# phasor.net
KiCad netlist of a schematic drawn in EAGLE
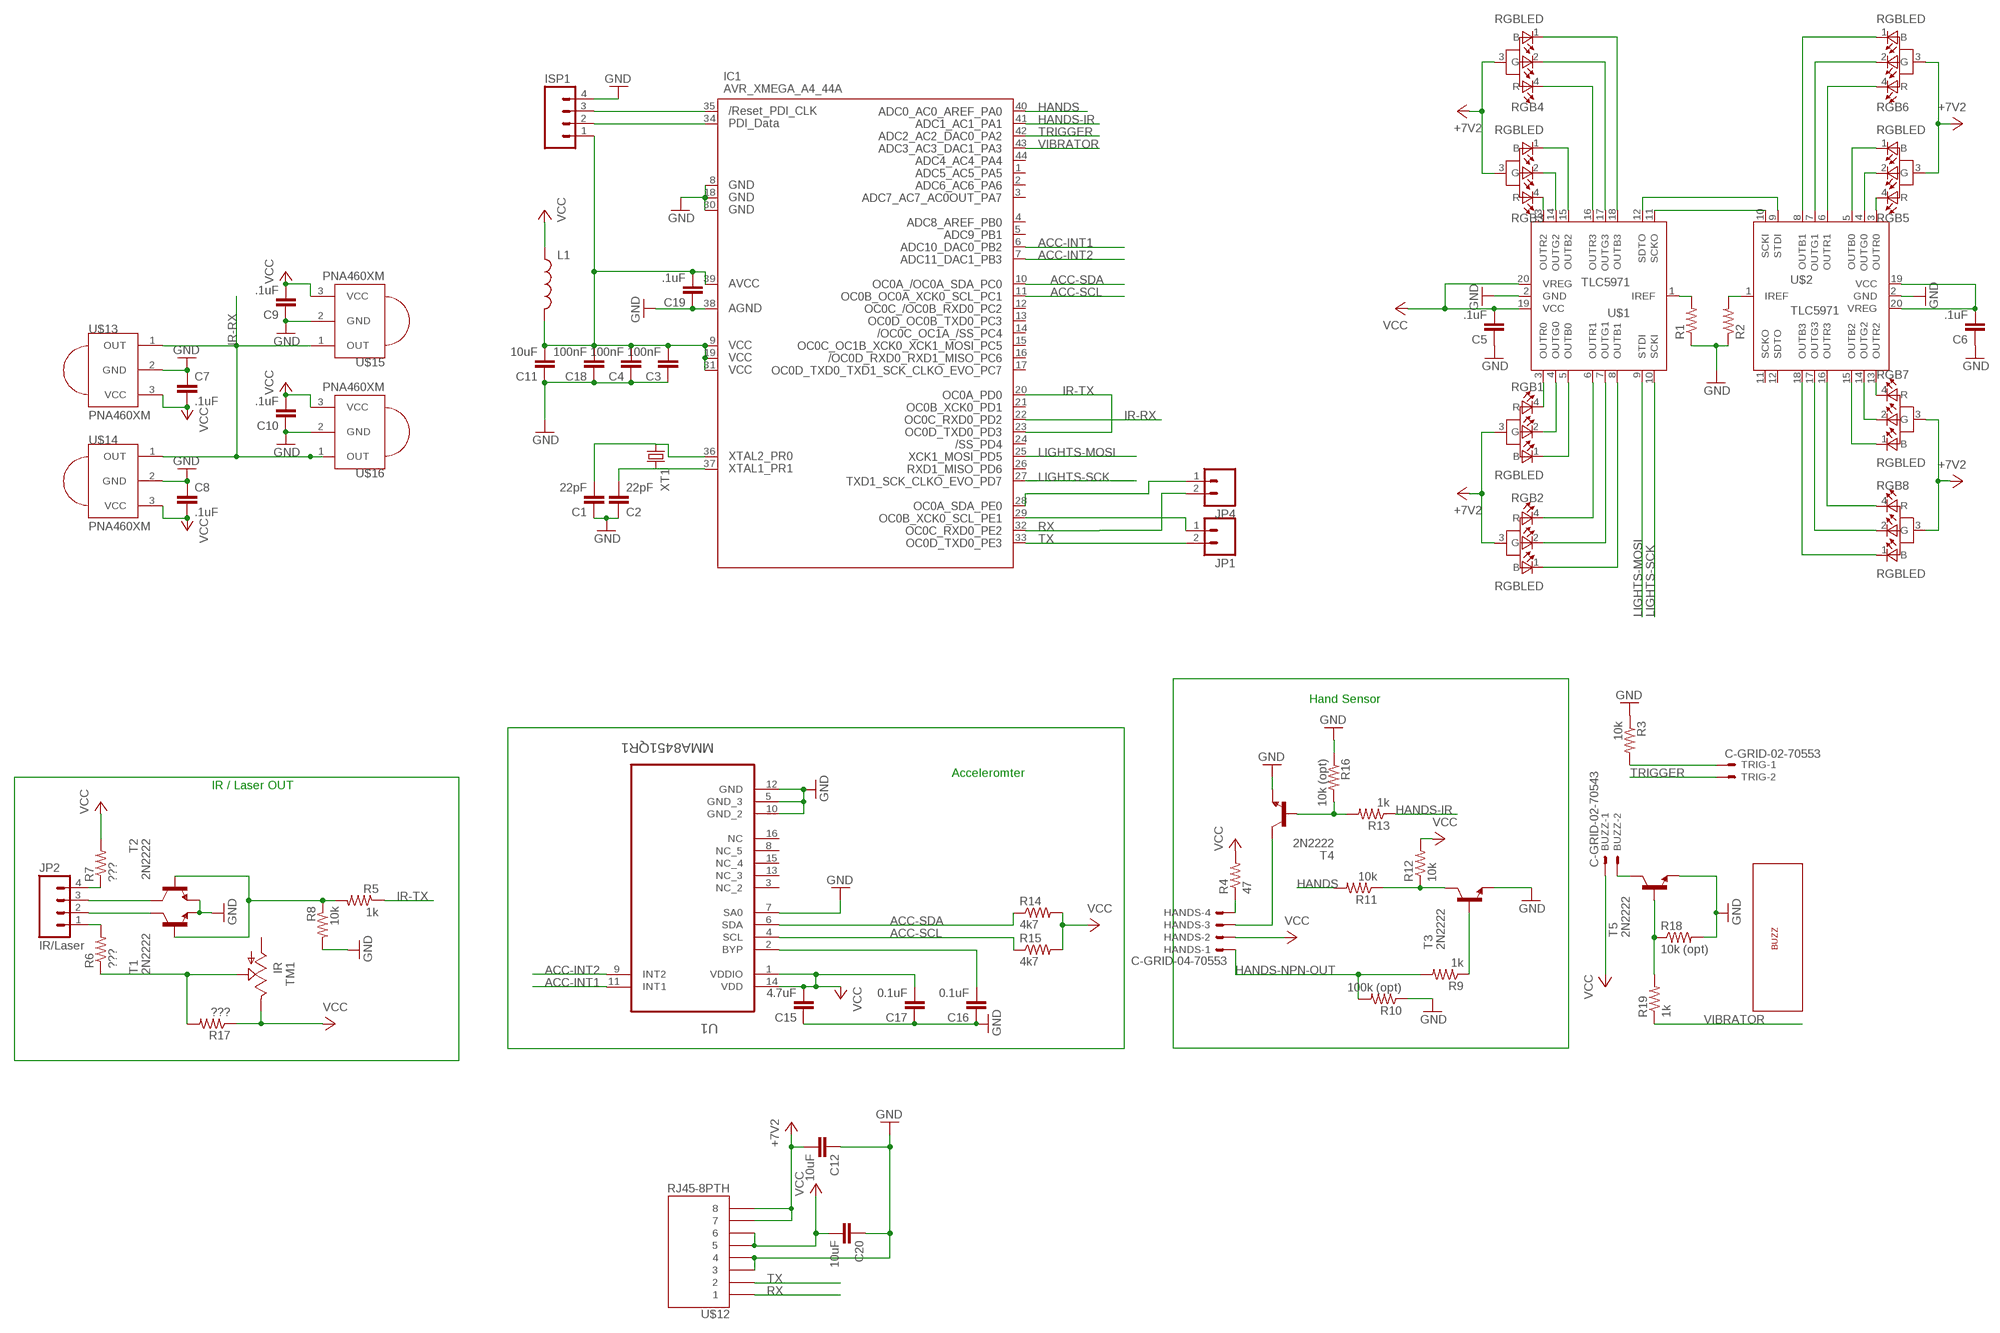
[diagram p0: schematic, sheet 1]

(export (version "E")
  (design (tool "Eeschema 10.0.6"))
  (components
    (comp (ref "BUZZ")
      (value "C-GRID-02-70543")
      (footprint "eagle-import:70543-02")
      (libsource (lib "eagle-import") (part "C-GRID-02-70543"))
    )
    (comp (ref "C1")
      (value "22pF")
      (footprint "eagle-import:CAP-PTH-SMALL")
      (libsource (lib "eagle-import") (part "CAPPTH"))
    )
    (comp (ref "C2")
      (value "22pF")
      (footprint "eagle-import:CAP-PTH-SMALL")
      (libsource (lib "eagle-import") (part "CAPPTH"))
    )
    (comp (ref "C3")
      (value "100nF")
      (footprint "eagle-import:0603-CAP")
      (libsource (lib "eagle-import") (part "CAP0603-CAP"))
    )
    (comp (ref "C4")
      (value "100nF")
      (footprint "eagle-import:0603-CAP")
      (libsource (lib "eagle-import") (part "CAP0603-CAP"))
    )
    (comp (ref "C5")
      (value ".1uF")
      (footprint "eagle-import:CAP-PTH-SMALL")
      (libsource (lib "eagle-import") (part "CAPPTH"))
    )
    (comp (ref "C6")
      (value ".1uF")
      (footprint "eagle-import:CAP-PTH-SMALL")
      (libsource (lib "eagle-import") (part "CAPPTH"))
    )
    (comp (ref "C7")
      (value ".1uF")
      (footprint "eagle-import:CAP-PTH-SMALL")
      (libsource (lib "eagle-import") (part "CAPPTH"))
    )
    (comp (ref "C8")
      (value ".1uF")
      (footprint "eagle-import:CAP-PTH-SMALL")
      (libsource (lib "eagle-import") (part "CAPPTH"))
    )
    (comp (ref "C9")
      (value ".1uF")
      (footprint "eagle-import:CAP-PTH-SMALL")
      (libsource (lib "eagle-import") (part "CAPPTH"))
    )
    (comp (ref "C10")
      (value ".1uF")
      (footprint "eagle-import:CAP-PTH-SMALL")
      (libsource (lib "eagle-import") (part "CAPPTH"))
    )
    (comp (ref "C11")
      (value "10uF")
      (footprint "eagle-import:1206")
      (libsource (lib "eagle-import") (part "CAP1206"))
    )
    (comp (ref "C12")
      (value "10uF")
      (footprint "eagle-import:1206")
      (libsource (lib "eagle-import") (part "CAP1206"))
    )
    (comp (ref "C15")
      (value "4.7uF")
      (footprint "eagle-import:0805")
      (libsource (lib "eagle-import") (part "CAP0805"))
    )
    (comp (ref "C16")
      (value "0.1uF")
      (footprint "eagle-import:0603-CAP")
      (libsource (lib "eagle-import") (part "CAP0603-CAP"))
    )
    (comp (ref "C17")
      (value "0.1uF")
      (footprint "eagle-import:0603-CAP")
      (libsource (lib "eagle-import") (part "CAP0603-CAP"))
    )
    (comp (ref "C18")
      (value "100nF")
      (footprint "eagle-import:0603-CAP")
      (libsource (lib "eagle-import") (part "CAP0603-CAP"))
    )
    (comp (ref "C19")
      (value ".1uF")
      (footprint "eagle-import:0603-CAP")
      (libsource (lib "eagle-import") (part "CAP0603-CAP"))
    )
    (comp (ref "C20")
      (value "10uF")
      (footprint "eagle-import:1206")
      (libsource (lib "eagle-import") (part "CAP1206"))
    )
    (comp (ref "HANDS")
      (value "C-GRID-04-70553")
      (footprint "eagle-import:70553-04")
      (libsource (lib "eagle-import") (part "C-GRID-04-70553"))
    )
    (comp (ref "IC1")
      (value "AVR_XMEGA_A4_44A")
      (footprint "eagle-import:TQFP44")
      (libsource (lib "eagle-import") (part "AVR_XMEGA_A4_44A"))
    )
    (comp (ref "ISP1")
      (value "M04LOCK")
      (footprint "eagle-import:1X04_LOCK")
      (libsource (lib "eagle-import") (part "M04LOCK"))
    )
    (comp (ref "JP1")
      (value "M02PTH")
      (footprint "eagle-import:1X02")
      (libsource (lib "eagle-import") (part "M02PTH"))
    )
    (comp (ref "JP2")
      (value "IR/Laser")
      (footprint "eagle-import:1X04_LOCK")
      (libsource (lib "eagle-import") (part "M04LOCK"))
    )
    (comp (ref "JP4")
      (value "M02PTH")
      (footprint "eagle-import:1X02")
      (libsource (lib "eagle-import") (part "M02PTH"))
    )
    (comp (ref "L1")
      (value "INDUCTOR1206H*")
      (footprint "eagle-import:1206")
      (libsource (lib "eagle-import") (part "INDUCTORH1206"))
    )
    (comp (ref "R1")
      (value "R-US_0204/7")
      (footprint "eagle-import:0204_7")
      (libsource (lib "eagle-import") (part "R-US_0204/7"))
    )
    (comp (ref "R2")
      (value "R-US_0204/7")
      (footprint "eagle-import:0204_7")
      (libsource (lib "eagle-import") (part "R-US_0204/7"))
    )
    (comp (ref "R3")
      (value "10k")
      (footprint "eagle-import:0204_7")
      (libsource (lib "eagle-import") (part "R-US_0204/7"))
    )
    (comp (ref "R4")
      (value "47")
      (footprint "eagle-import:0204_7")
      (libsource (lib "eagle-import") (part "R-US_0204/7"))
    )
    (comp (ref "R5")
      (value "1k")
      (footprint "eagle-import:0204_7")
      (libsource (lib "eagle-import") (part "R-US_0204/7"))
    )
    (comp (ref "R6")
      (value "???")
      (footprint "eagle-import:0204_7")
      (libsource (lib "eagle-import") (part "R-US_0204/7"))
    )
    (comp (ref "R7")
      (value "???")
      (footprint "eagle-import:0204_7")
      (libsource (lib "eagle-import") (part "R-US_0204/7"))
    )
    (comp (ref "R8")
      (value "10k")
      (footprint "eagle-import:0204_7")
      (libsource (lib "eagle-import") (part "R-US_0204/7"))
    )
    (comp (ref "R9")
      (value "1k")
      (footprint "eagle-import:0204_7")
      (libsource (lib "eagle-import") (part "R-US_0204/7"))
    )
    (comp (ref "R10")
      (value "100k (opt)")
      (footprint "eagle-import:0204_7")
      (libsource (lib "eagle-import") (part "R-US_0204/7"))
    )
    (comp (ref "R11")
      (value "10k")
      (footprint "eagle-import:0204_7")
      (libsource (lib "eagle-import") (part "R-US_0204/7"))
    )
    (comp (ref "R12")
      (value "10k")
      (footprint "eagle-import:0204_7")
      (libsource (lib "eagle-import") (part "R-US_0204/7"))
    )
    (comp (ref "R13")
      (value "1k")
      (footprint "eagle-import:0204_7")
      (libsource (lib "eagle-import") (part "R-US_0204/7"))
    )
    (comp (ref "R14")
      (value "4k7")
      (footprint "eagle-import:0204_7")
      (libsource (lib "eagle-import") (part "R-US_0204/7"))
    )
    (comp (ref "R15")
      (value "4k7")
      (footprint "eagle-import:0204_7")
      (libsource (lib "eagle-import") (part "R-US_0204/7"))
    )
    (comp (ref "R16")
      (value "10k (opt)")
      (footprint "eagle-import:0204_7")
      (libsource (lib "eagle-import") (part "R-US_0204/7"))
    )
    (comp (ref "R17")
      (value "???")
      (footprint "eagle-import:0204_7")
      (libsource (lib "eagle-import") (part "R-US_0204/7"))
    )
    (comp (ref "R18")
      (value "10k (opt)")
      (footprint "eagle-import:0204_7")
      (libsource (lib "eagle-import") (part "R-US_0204/7"))
    )
    (comp (ref "R19")
      (value "1k")
      (footprint "eagle-import:0204_7")
      (libsource (lib "eagle-import") (part "R-US_0204/7"))
    )
    (comp (ref "RGB1")
      (value "RGBLED")
      (footprint "eagle-import:RGB-LED-10MM-COMMON-ANODE")
      (libsource (lib "eagle-import") (part "RGBLED"))
    )
    (comp (ref "RGB2")
      (value "RGBLED")
      (footprint "eagle-import:RGB-LED-10MM-COMMON-ANODE")
      (libsource (lib "eagle-import") (part "RGBLED"))
    )
    (comp (ref "RGB3")
      (value "RGBLED")
      (footprint "eagle-import:RGB-LED-10MM-COMMON-ANODE")
      (libsource (lib "eagle-import") (part "RGBLED"))
    )
    (comp (ref "RGB4")
      (value "RGBLED")
      (footprint "eagle-import:RGB-LED-10MM-COMMON-ANODE")
      (libsource (lib "eagle-import") (part "RGBLED"))
    )
    (comp (ref "RGB5")
      (value "RGBLED")
      (footprint "eagle-import:RGB-LED-10MM-COMMON-ANODE")
      (libsource (lib "eagle-import") (part "RGBLED"))
    )
    (comp (ref "RGB6")
      (value "RGBLED")
      (footprint "eagle-import:RGB-LED-10MM-COMMON-ANODE")
      (libsource (lib "eagle-import") (part "RGBLED"))
    )
    (comp (ref "RGB7")
      (value "RGBLED")
      (footprint "eagle-import:RGB-LED-10MM-COMMON-ANODE")
      (libsource (lib "eagle-import") (part "RGBLED"))
    )
    (comp (ref "RGB8")
      (value "RGBLED")
      (footprint "eagle-import:RGB-LED-10MM-COMMON-ANODE")
      (libsource (lib "eagle-import") (part "RGBLED"))
    )
    (comp (ref "T1")
      (value "2N2222")
      (footprint "eagle-import:TO92-EBC-OVAL")
      (libsource (lib "eagle-import") (part "2N2222"))
    )
    (comp (ref "T2")
      (value "2N2222")
      (footprint "eagle-import:TO92-EBC-OVAL")
      (libsource (lib "eagle-import") (part "2N2222"))
    )
    (comp (ref "T3")
      (value "2N2222")
      (footprint "eagle-import:TO92-EBC-OVAL")
      (libsource (lib "eagle-import") (part "2N2222"))
    )
    (comp (ref "T4")
      (value "2N2222")
      (footprint "eagle-import:TO92-EBC-OVAL")
      (libsource (lib "eagle-import") (part "2N2222"))
    )
    (comp (ref "T5")
      (value "2N2222")
      (footprint "eagle-import:TO92-EBC-OVAL")
      (libsource (lib "eagle-import") (part "2N2222"))
    )
    (comp (ref "TM1")
      (value "IR")
      (footprint "eagle-import:B25P")
      (libsource (lib "eagle-import") (part "TRIM_US-B25P"))
    )
    (comp (ref "TRIG")
      (value "C-GRID-02-70553")
      (footprint "eagle-import:70553-02")
      (libsource (lib "eagle-import") (part "C-GRID-02-70553"))
    )
    (comp (ref "U$1")
      (value "TLC5971")
      (footprint "eagle-import:SSOP20")
      (libsource (lib "eagle-import") (part "TLC5971"))
    )
    (comp (ref "U$2")
      (value "TLC5971")
      (footprint "eagle-import:SSOP20")
      (libsource (lib "eagle-import") (part "TLC5971"))
    )
    (comp (ref "U$3")
      (value "VIB-CAPSULE")
      (footprint "eagle-import:VIB-CAPSULE")
      (libsource (lib "eagle-import") (part "VIB-CAPSULE"))
    )
    (comp (ref "U$12")
      (value "RJ45-8PTH")
      (footprint "eagle-import:RJ45-8")
      (libsource (lib "eagle-import") (part "RJ45-8PTH"))
    )
    (comp (ref "U$13")
      (value "PNA460XM")
      (footprint "eagle-import:PNA460XM")
      (libsource (lib "eagle-import") (part "PNA460XM"))
    )
    (comp (ref "U$14")
      (value "PNA460XM")
      (footprint "eagle-import:PNA460XM")
      (libsource (lib "eagle-import") (part "PNA460XM"))
    )
    (comp (ref "U$15")
      (value "PNA460XM")
      (footprint "eagle-import:PNA460XM")
      (libsource (lib "eagle-import") (part "PNA460XM"))
    )
    (comp (ref "U$16")
      (value "PNA460XM")
      (footprint "eagle-import:PNA460XM")
      (libsource (lib "eagle-import") (part "PNA460XM"))
    )
    (comp (ref "U1")
      (value "MMA8451QR1")
      (footprint "eagle-import:QFN50P300X300X100-16N")
      (libsource (lib "eagle-import") (part "MMA8451QR1"))
    )
    (comp (ref "XT1")
      (value "CRYSTALHC49US")
      (footprint "eagle-import:HC49US")
      (libsource (lib "eagle-import") (part "CRYSTALHC49US"))
    )
  )
  (nets
    (net (code "1") (name "/+7V2") (class "Default")
      (node (ref "C12") (pin "2") (pinfunction "2_2") (pintype "passive"))
      (node (ref "RGB1") (pin "3") (pinfunction "VCC_3") (pintype "passive"))
      (node (ref "RGB2") (pin "3") (pinfunction "VCC_3") (pintype "passive"))
      (node (ref "RGB3") (pin "3") (pinfunction "VCC_3") (pintype "passive"))
      (node (ref "RGB4") (pin "3") (pinfunction "VCC_3") (pintype "passive"))
      (node (ref "RGB5") (pin "3") (pinfunction "VCC_3") (pintype "passive"))
      (node (ref "RGB6") (pin "3") (pinfunction "VCC_3") (pintype "passive"))
      (node (ref "RGB7") (pin "3") (pinfunction "VCC_3") (pintype "passive"))
      (node (ref "RGB8") (pin "3") (pinfunction "VCC_3") (pintype "passive"))
      (node (ref "U$12") (pin "7") (pinfunction "7_7") (pintype "bidirectional"))
      (node (ref "U$12") (pin "8") (pinfunction "8_8") (pintype "bidirectional"))
    )
    (net (code "2") (name "/ACC-INT1") (class "Default")
      (node (ref "IC1") (pin "6") (pinfunction "PB2_6") (pintype "bidirectional"))
      (node (ref "U1") (pin "11") (pinfunction "INT1_11") (pintype "output"))
    )
    (net (code "3") (name "/ACC-INT2") (class "Default")
      (node (ref "IC1") (pin "7") (pinfunction "PB3_7") (pintype "bidirectional"))
      (node (ref "U1") (pin "9") (pinfunction "INT2_9") (pintype "output"))
    )
    (net (code "4") (name "/ACC-SCL") (class "Default")
      (node (ref "IC1") (pin "11") (pinfunction "PC1_11") (pintype "bidirectional"))
      (node (ref "R15") (pin "1") (pinfunction "1_1") (pintype "passive"))
      (node (ref "U1") (pin "4") (pinfunction "SCL_4") (pintype "input"))
    )
    (net (code "5") (name "/ACC-SDA") (class "Default")
      (node (ref "IC1") (pin "10") (pinfunction "PC0_10") (pintype "bidirectional"))
      (node (ref "R14") (pin "1") (pinfunction "1_1") (pintype "passive"))
      (node (ref "U1") (pin "6") (pinfunction "SDA_6") (pintype "input"))
    )
    (net (code "6") (name "/HANDS") (class "Default")
      (node (ref "IC1") (pin "40") (pinfunction "PA0_40") (pintype "bidirectional"))
      (node (ref "R11") (pin "2") (pinfunction "2_2") (pintype "passive"))
    )
    (net (code "7") (name "/HANDS-IR") (class "Default")
      (node (ref "IC1") (pin "41") (pinfunction "PA1_41") (pintype "bidirectional"))
      (node (ref "R13") (pin "1") (pinfunction "1_1") (pintype "passive"))
    )
    (net (code "8") (name "/HANDS-NPN-OUT") (class "Default")
      (node (ref "HANDS") (pin "1") (pinfunction "S_1") (pintype "passive"))
      (node (ref "R10") (pin "2") (pinfunction "2_2") (pintype "passive"))
      (node (ref "R9") (pin "2") (pinfunction "2_2") (pintype "passive"))
    )
    (net (code "9") (name "/IR-RX") (class "Default")
      (node (ref "IC1") (pin "22") (pinfunction "PD2_22") (pintype "bidirectional"))
      (node (ref "U$13") (pin "1") (pinfunction "OUT_1") (pintype "output"))
      (node (ref "U$14") (pin "1") (pinfunction "OUT_1") (pintype "output"))
      (node (ref "U$15") (pin "1") (pinfunction "OUT_1") (pintype "output"))
      (node (ref "U$16") (pin "1") (pinfunction "OUT_1") (pintype "output"))
    )
    (net (code "10") (name "/IR-TX") (class "Default")
      (node (ref "IC1") (pin "20") (pinfunction "PD0_20") (pintype "bidirectional"))
      (node (ref "IC1") (pin "23") (pinfunction "PD3_23") (pintype "bidirectional"))
      (node (ref "R5") (pin "1") (pinfunction "1_1") (pintype "passive"))
    )
    (net (code "11") (name "/LIGHTS-MOSI") (class "Default")
      (node (ref "IC1") (pin "25") (pinfunction "PD5_25") (pintype "bidirectional"))
      (node (ref "U$1") (pin "9") (pinfunction "STDI_9") (pintype "bidirectional"))
    )
    (net (code "12") (name "/LIGHTS-SCK") (class "Default")
      (node (ref "IC1") (pin "27") (pinfunction "PD7_27") (pintype "bidirectional"))
      (node (ref "U$1") (pin "10") (pinfunction "SCKI_10") (pintype "bidirectional"))
    )
    (net (code "13") (name "/RX") (class "Default")
      (node (ref "IC1") (pin "32") (pinfunction "PE2_32") (pintype "bidirectional"))
      (node (ref "JP4") (pin "2") (pinfunction "2_2") (pintype "passive"))
      (node (ref "U$12") (pin "1") (pinfunction "1_1") (pintype "bidirectional"))
    )
    (net (code "14") (name "/TRIGGER") (class "Default")
      (node (ref "IC1") (pin "42") (pinfunction "PA2_42") (pintype "bidirectional"))
      (node (ref "TRIG") (pin "2") (pinfunction "S_2") (pintype "passive"))
    )
    (net (code "15") (name "/TX") (class "Default")
      (node (ref "IC1") (pin "33") (pinfunction "PE3_33") (pintype "bidirectional"))
      (node (ref "JP1") (pin "2") (pinfunction "2_2") (pintype "passive"))
      (node (ref "U$12") (pin "2") (pinfunction "2_2") (pintype "bidirectional"))
    )
    (net (code "16") (name "/VIBRATOR") (class "Default")
      (node (ref "IC1") (pin "43") (pinfunction "PA3_43") (pintype "bidirectional"))
      (node (ref "R19") (pin "1") (pinfunction "1_1") (pintype "passive"))
    )
    (net (code "17") (name "GND") (class "Default")
      (node (ref "C1") (pin "1") (pinfunction "1_1") (pintype "passive"))
      (node (ref "C10") (pin "1") (pinfunction "1_1") (pintype "passive"))
      (node (ref "C11") (pin "1") (pinfunction "1_1") (pintype "passive"))
      (node (ref "C12") (pin "1") (pinfunction "1_1") (pintype "passive"))
      (node (ref "C15") (pin "1") (pinfunction "1_1") (pintype "passive"))
      (node (ref "C16") (pin "1") (pinfunction "1_1") (pintype "passive"))
      (node (ref "C17") (pin "1") (pinfunction "1_1") (pintype "passive"))
      (node (ref "C18") (pin "1") (pinfunction "1_1") (pintype "passive"))
      (node (ref "C19") (pin "1") (pinfunction "1_1") (pintype "passive"))
      (node (ref "C2") (pin "1") (pinfunction "1_1") (pintype "passive"))
      (node (ref "C20") (pin "1") (pinfunction "1_1") (pintype "passive"))
      (node (ref "C3") (pin "1") (pinfunction "1_1") (pintype "passive"))
      (node (ref "C4") (pin "1") (pinfunction "1_1") (pintype "passive"))
      (node (ref "C5") (pin "1") (pinfunction "1_1") (pintype "passive"))
      (node (ref "C6") (pin "1") (pinfunction "1_1") (pintype "passive"))
      (node (ref "C7") (pin "1") (pinfunction "1_1") (pintype "passive"))
      (node (ref "C8") (pin "1") (pinfunction "1_1") (pintype "passive"))
      (node (ref "C9") (pin "1") (pinfunction "1_1") (pintype "passive"))
      (node (ref "IC1") (pin "18") (pinfunction "GND2_18") (pintype "bidirectional"))
      (node (ref "IC1") (pin "30") (pinfunction "GND3_30") (pintype "bidirectional"))
      (node (ref "IC1") (pin "38") (pinfunction "AGND_38") (pintype "bidirectional"))
      (node (ref "IC1") (pin "8") (pinfunction "GND1_8") (pintype "bidirectional"))
      (node (ref "ISP1") (pin "4") (pinfunction "4_4") (pintype "passive"))
      (node (ref "R1") (pin "1") (pinfunction "1_1") (pintype "passive"))
      (node (ref "R10") (pin "1") (pinfunction "1_1") (pintype "passive"))
      (node (ref "R16") (pin "1") (pinfunction "1_1") (pintype "passive"))
      (node (ref "R18") (pin "2") (pinfunction "2_2") (pintype "passive"))
      (node (ref "R2") (pin "1") (pinfunction "1_1") (pintype "passive"))
      (node (ref "R3") (pin "1") (pinfunction "1_1") (pintype "passive"))
      (node (ref "R8") (pin "2") (pinfunction "2_2") (pintype "passive"))
      (node (ref "T1") (pin "E") (pinfunction "E_E") (pintype "passive"))
      (node (ref "T2") (pin "E") (pinfunction "E_E") (pintype "passive"))
      (node (ref "T3") (pin "E") (pinfunction "E_E") (pintype "passive"))
      (node (ref "T4") (pin "E") (pinfunction "E_E") (pintype "passive"))
      (node (ref "T5") (pin "E") (pinfunction "E_E") (pintype "passive"))
      (node (ref "U$1") (pin "2") (pinfunction "GND_2") (pintype "power_in"))
      (node (ref "U$12") (pin "3") (pinfunction "3_3") (pintype "bidirectional"))
      (node (ref "U$12") (pin "4") (pinfunction "4_4") (pintype "bidirectional"))
      (node (ref "U$13") (pin "2") (pinfunction "GND_2") (pintype "power_in"))
      (node (ref "U$14") (pin "2") (pinfunction "GND_2") (pintype "power_in"))
      (node (ref "U$15") (pin "2") (pinfunction "GND_2") (pintype "power_in"))
      (node (ref "U$16") (pin "2") (pinfunction "GND_2") (pintype "power_in"))
      (node (ref "U$2") (pin "2") (pinfunction "GND_2") (pintype "power_in"))
      (node (ref "U1") (pin "10") (pinfunction "GND_2_10") (pintype "passive"))
      (node (ref "U1") (pin "12") (pinfunction "GND_12") (pintype "passive"))
      (node (ref "U1") (pin "5") (pinfunction "GND_3_5") (pintype "passive"))
      (node (ref "U1") (pin "7") (pinfunction "SA0_7") (pintype "input"))
    )
    (net (code "18") (name "Net-(BUZZB-S)") (class "Default")
      (node (ref "BUZZ") (pin "2") (pinfunction "S_2") (pintype "passive"))
      (node (ref "T5") (pin "C") (pinfunction "C_C") (pintype "passive"))
    )
    (net (code "19") (name "Net-(HANDSC-S)") (class "Default")
      (node (ref "HANDS") (pin "3") (pinfunction "S_3") (pintype "passive"))
      (node (ref "T4") (pin "C") (pinfunction "C_C") (pintype "passive"))
    )
    (net (code "20") (name "Net-(HANDSD-S)") (class "Default")
      (node (ref "HANDS") (pin "4") (pinfunction "S_4") (pintype "passive"))
      (node (ref "R4") (pin "1") (pinfunction "1_1") (pintype "passive"))
    )
    (net (code "21") (name "Net-(IC1-AVCC)") (class "Default")
      (node (ref "C11") (pin "2") (pinfunction "2_2") (pintype "passive"))
      (node (ref "C18") (pin "2") (pinfunction "2_2") (pintype "passive"))
      (node (ref "C19") (pin "2") (pinfunction "2_2") (pintype "passive"))
      (node (ref "C3") (pin "2") (pinfunction "2_2") (pintype "passive"))
      (node (ref "C4") (pin "2") (pinfunction "2_2") (pintype "passive"))
      (node (ref "IC1") (pin "19") (pinfunction "VCC2_19") (pintype "bidirectional"))
      (node (ref "IC1") (pin "31") (pinfunction "VCC3_31") (pintype "bidirectional"))
      (node (ref "IC1") (pin "39") (pinfunction "AVCC_39") (pintype "bidirectional"))
      (node (ref "IC1") (pin "9") (pinfunction "VCC1_9") (pintype "bidirectional"))
      (node (ref "ISP1") (pin "1") (pinfunction "1_1") (pintype "passive"))
      (node (ref "L1") (pin "2") (pinfunction "2_2") (pintype "passive"))
    )
    (net (code "22") (name "Net-(IC1-PDI_DATA)") (class "Default")
      (node (ref "IC1") (pin "34") (pinfunction "PDI_DATA_34") (pintype "bidirectional"))
      (node (ref "ISP1") (pin "2") (pinfunction "2_2") (pintype "passive"))
    )
    (net (code "23") (name "Net-(IC1-PE0)") (class "Default")
      (node (ref "IC1") (pin "28") (pinfunction "PE0_28") (pintype "bidirectional"))
      (node (ref "JP4") (pin "1") (pinfunction "1_1") (pintype "passive"))
    )
    (net (code "24") (name "Net-(IC1-PE1)") (class "Default")
      (node (ref "IC1") (pin "29") (pinfunction "PE1_29") (pintype "bidirectional"))
      (node (ref "JP1") (pin "1") (pinfunction "1_1") (pintype "passive"))
    )
    (net (code "25") (name "Net-(IC1-PR0)") (class "Default")
      (node (ref "C1") (pin "2") (pinfunction "2_2") (pintype "passive"))
      (node (ref "IC1") (pin "36") (pinfunction "PR0_36") (pintype "bidirectional"))
      (node (ref "XT1") (pin "1") (pinfunction "1_1") (pintype "passive"))
    )
    (net (code "26") (name "Net-(IC1-PR1)") (class "Default")
      (node (ref "C2") (pin "2") (pinfunction "2_2") (pintype "passive"))
      (node (ref "IC1") (pin "37") (pinfunction "PR1_37") (pintype "bidirectional"))
      (node (ref "XT1") (pin "2") (pinfunction "2_2") (pintype "passive"))
    )
    (net (code "27") (name "Net-(IC1-RESET)") (class "Default")
      (node (ref "IC1") (pin "35") (pinfunction "RESET_35") (pintype "bidirectional"))
      (node (ref "ISP1") (pin "3") (pinfunction "3_3") (pintype "passive"))
    )
    (net (code "28") (name "Net-(JP2-Pad1)") (class "Default")
      (node (ref "JP2") (pin "1") (pinfunction "1_1") (pintype "passive"))
      (node (ref "R6") (pin "2") (pinfunction "2_2") (pintype "passive"))
    )
    (net (code "29") (name "Net-(JP2-Pad2)") (class "Default")
      (node (ref "JP2") (pin "2") (pinfunction "2_2") (pintype "passive"))
      (node (ref "T1") (pin "C") (pinfunction "C_C") (pintype "passive"))
    )
    (net (code "30") (name "Net-(JP2-Pad3)") (class "Default")
      (node (ref "JP2") (pin "3") (pinfunction "3_3") (pintype "passive"))
      (node (ref "T2") (pin "C") (pinfunction "C_C") (pintype "passive"))
    )
    (net (code "31") (name "Net-(JP2-Pad4)") (class "Default")
      (node (ref "JP2") (pin "4") (pinfunction "4_4") (pintype "passive"))
      (node (ref "R7") (pin "1") (pinfunction "1_1") (pintype "passive"))
    )
    (net (code "32") (name "Net-(R5-Pad2)") (class "Default")
      (node (ref "R5") (pin "2") (pinfunction "2_2") (pintype "passive"))
      (node (ref "R8") (pin "1") (pinfunction "1_1") (pintype "passive"))
      (node (ref "T1") (pin "B") (pinfunction "B_B") (pintype "passive"))
      (node (ref "T2") (pin "B") (pinfunction "B_B") (pintype "passive"))
    )
    (net (code "33") (name "Net-(R9-Pad1)") (class "Default")
      (node (ref "R9") (pin "1") (pinfunction "1_1") (pintype "passive"))
      (node (ref "T3") (pin "B") (pinfunction "B_B") (pintype "passive"))
    )
    (net (code "34") (name "Net-(R11-Pad1)") (class "Default")
      (node (ref "R11") (pin "1") (pinfunction "1_1") (pintype "passive"))
      (node (ref "R12") (pin "1") (pinfunction "1_1") (pintype "passive"))
      (node (ref "T3") (pin "C") (pinfunction "C_C") (pintype "passive"))
    )
    (net (code "35") (name "Net-(R13-Pad2)") (class "Default")
      (node (ref "R13") (pin "2") (pinfunction "2_2") (pintype "passive"))
      (node (ref "R16") (pin "2") (pinfunction "2_2") (pintype "passive"))
      (node (ref "T4") (pin "B") (pinfunction "B_B") (pintype "passive"))
    )
    (net (code "36") (name "Net-(R17-Pad2)") (class "Default")
      (node (ref "R17") (pin "2") (pinfunction "2_2") (pintype "passive"))
      (node (ref "R6") (pin "1") (pinfunction "1_1") (pintype "passive"))
      (node (ref "TM1") (pin "S") (pinfunction "S_S") (pintype "passive"))
    )
    (net (code "37") (name "Net-(R18-Pad1)") (class "Default")
      (node (ref "R18") (pin "1") (pinfunction "1_1") (pintype "passive"))
      (node (ref "R19") (pin "2") (pinfunction "2_2") (pintype "passive"))
      (node (ref "T5") (pin "B") (pinfunction "B_B") (pintype "passive"))
    )
    (net (code "38") (name "Net-(RGB1-B)") (class "Default")
      (node (ref "RGB1") (pin "1") (pinfunction "B_1") (pintype "passive"))
      (node (ref "U$1") (pin "5") (pinfunction "OUTB0_5") (pintype "bidirectional"))
    )
    (net (code "39") (name "Net-(RGB1-G)") (class "Default")
      (node (ref "RGB1") (pin "2") (pinfunction "G_2") (pintype "passive"))
      (node (ref "U$1") (pin "4") (pinfunction "OUTG0_4") (pintype "bidirectional"))
    )
    (net (code "40") (name "Net-(RGB1-R)") (class "Default")
      (node (ref "RGB1") (pin "4") (pinfunction "R_4") (pintype "passive"))
      (node (ref "U$1") (pin "3") (pinfunction "OUTR0_3") (pintype "bidirectional"))
    )
    (net (code "41") (name "Net-(RGB2-B)") (class "Default")
      (node (ref "RGB2") (pin "1") (pinfunction "B_1") (pintype "passive"))
      (node (ref "U$1") (pin "8") (pinfunction "OUTB1_8") (pintype "bidirectional"))
    )
    (net (code "42") (name "Net-(RGB2-G)") (class "Default")
      (node (ref "RGB2") (pin "2") (pinfunction "G_2") (pintype "passive"))
      (node (ref "U$1") (pin "7") (pinfunction "OUTG1_7") (pintype "bidirectional"))
    )
    (net (code "43") (name "Net-(RGB2-R)") (class "Default")
      (node (ref "RGB2") (pin "4") (pinfunction "R_4") (pintype "passive"))
      (node (ref "U$1") (pin "6") (pinfunction "OUTR1_6") (pintype "bidirectional"))
    )
    (net (code "44") (name "Net-(RGB3-B)") (class "Default")
      (node (ref "RGB3") (pin "1") (pinfunction "B_1") (pintype "passive"))
      (node (ref "U$1") (pin "15") (pinfunction "OUTB2_15") (pintype "bidirectional"))
    )
    (net (code "45") (name "Net-(RGB3-G)") (class "Default")
      (node (ref "RGB3") (pin "2") (pinfunction "G_2") (pintype "passive"))
      (node (ref "U$1") (pin "14") (pinfunction "OUTG2_14") (pintype "bidirectional"))
    )
    (net (code "46") (name "Net-(RGB3-R)") (class "Default")
      (node (ref "RGB3") (pin "4") (pinfunction "R_4") (pintype "passive"))
      (node (ref "U$1") (pin "13") (pinfunction "OUTR2_13") (pintype "bidirectional"))
    )
    (net (code "47") (name "Net-(RGB4-B)") (class "Default")
      (node (ref "RGB4") (pin "1") (pinfunction "B_1") (pintype "passive"))
      (node (ref "U$1") (pin "18") (pinfunction "OUTB3_18") (pintype "bidirectional"))
    )
    (net (code "48") (name "Net-(RGB4-G)") (class "Default")
      (node (ref "RGB4") (pin "2") (pinfunction "G_2") (pintype "passive"))
      (node (ref "U$1") (pin "17") (pinfunction "OUTG3_17") (pintype "bidirectional"))
    )
    (net (code "49") (name "Net-(RGB4-R)") (class "Default")
      (node (ref "RGB4") (pin "4") (pinfunction "R_4") (pintype "passive"))
      (node (ref "U$1") (pin "16") (pinfunction "OUTR3_16") (pintype "bidirectional"))
    )
    (net (code "50") (name "Net-(RGB5-B)") (class "Default")
      (node (ref "RGB5") (pin "1") (pinfunction "B_1") (pintype "passive"))
      (node (ref "U$2") (pin "5") (pinfunction "OUTB0_5") (pintype "bidirectional"))
    )
    (net (code "51") (name "Net-(RGB5-G)") (class "Default")
      (node (ref "RGB5") (pin "2") (pinfunction "G_2") (pintype "passive"))
      (node (ref "U$2") (pin "4") (pinfunction "OUTG0_4") (pintype "bidirectional"))
    )
    (net (code "52") (name "Net-(RGB5-R)") (class "Default")
      (node (ref "RGB5") (pin "4") (pinfunction "R_4") (pintype "passive"))
      (node (ref "U$2") (pin "3") (pinfunction "OUTR0_3") (pintype "bidirectional"))
    )
    (net (code "53") (name "Net-(RGB6-B)") (class "Default")
      (node (ref "RGB6") (pin "1") (pinfunction "B_1") (pintype "passive"))
      (node (ref "U$2") (pin "8") (pinfunction "OUTB1_8") (pintype "bidirectional"))
    )
    (net (code "54") (name "Net-(RGB6-G)") (class "Default")
      (node (ref "RGB6") (pin "2") (pinfunction "G_2") (pintype "passive"))
      (node (ref "U$2") (pin "7") (pinfunction "OUTG1_7") (pintype "bidirectional"))
    )
    (net (code "55") (name "Net-(RGB6-R)") (class "Default")
      (node (ref "RGB6") (pin "4") (pinfunction "R_4") (pintype "passive"))
      (node (ref "U$2") (pin "6") (pinfunction "OUTR1_6") (pintype "bidirectional"))
    )
    (net (code "56") (name "Net-(RGB7-B)") (class "Default")
      (node (ref "RGB7") (pin "1") (pinfunction "B_1") (pintype "passive"))
      (node (ref "U$2") (pin "15") (pinfunction "OUTB2_15") (pintype "bidirectional"))
    )
    (net (code "57") (name "Net-(RGB7-G)") (class "Default")
      (node (ref "RGB7") (pin "2") (pinfunction "G_2") (pintype "passive"))
      (node (ref "U$2") (pin "14") (pinfunction "OUTG2_14") (pintype "bidirectional"))
    )
    (net (code "58") (name "Net-(RGB7-R)") (class "Default")
      (node (ref "RGB7") (pin "4") (pinfunction "R_4") (pintype "passive"))
      (node (ref "U$2") (pin "13") (pinfunction "OUTR2_13") (pintype "bidirectional"))
    )
    (net (code "59") (name "Net-(RGB8-B)") (class "Default")
      (node (ref "RGB8") (pin "1") (pinfunction "B_1") (pintype "passive"))
      (node (ref "U$2") (pin "18") (pinfunction "OUTB3_18") (pintype "bidirectional"))
    )
    (net (code "60") (name "Net-(RGB8-G)") (class "Default")
      (node (ref "RGB8") (pin "2") (pinfunction "G_2") (pintype "passive"))
      (node (ref "U$2") (pin "17") (pinfunction "OUTG3_17") (pintype "bidirectional"))
    )
    (net (code "61") (name "Net-(RGB8-R)") (class "Default")
      (node (ref "RGB8") (pin "4") (pinfunction "R_4") (pintype "passive"))
      (node (ref "U$2") (pin "16") (pinfunction "OUTR3_16") (pintype "bidirectional"))
    )
    (net (code "62") (name "Net-(TRIGA-S)") (class "Default")
      (node (ref "R3") (pin "2") (pinfunction "2_2") (pintype "passive"))
      (node (ref "TRIG") (pin "1") (pinfunction "S_1") (pintype "passive"))
    )
    (net (code "63") (name "Net-(U$1-IREF)") (class "Default")
      (node (ref "R1") (pin "2") (pinfunction "2_2") (pintype "passive"))
      (node (ref "U$1") (pin "1") (pinfunction "IREF_1") (pintype "bidirectional"))
    )
    (net (code "64") (name "Net-(U$1-SCKO)") (class "Default")
      (node (ref "U$1") (pin "11") (pinfunction "SCKO_11") (pintype "bidirectional"))
      (node (ref "U$2") (pin "10") (pinfunction "SCKI_10") (pintype "bidirectional"))
    )
    (net (code "65") (name "Net-(U$1-SDTO)") (class "Default")
      (node (ref "U$1") (pin "12") (pinfunction "SDTO_12") (pintype "bidirectional"))
      (node (ref "U$2") (pin "9") (pinfunction "STDI_9") (pintype "bidirectional"))
    )
    (net (code "66") (name "Net-(U$2-IREF)") (class "Default")
      (node (ref "R2") (pin "2") (pinfunction "2_2") (pintype "passive"))
      (node (ref "U$2") (pin "1") (pinfunction "IREF_1") (pintype "bidirectional"))
    )
    (net (code "67") (name "Net-(U1-BYP)") (class "Default")
      (node (ref "C16") (pin "2") (pinfunction "2_2") (pintype "passive"))
      (node (ref "U1") (pin "2") (pinfunction "BYP_2") (pintype "input"))
    )
    (net (code "68") (name "VCC") (class "Default")
      (node (ref "BUZZ") (pin "1") (pinfunction "S_1") (pintype "passive"))
      (node (ref "C10") (pin "2") (pinfunction "2_2") (pintype "passive"))
      (node (ref "C15") (pin "2") (pinfunction "2_2") (pintype "passive"))
      (node (ref "C17") (pin "2") (pinfunction "2_2") (pintype "passive"))
      (node (ref "C20") (pin "2") (pinfunction "2_2") (pintype "passive"))
      (node (ref "C5") (pin "2") (pinfunction "2_2") (pintype "passive"))
      (node (ref "C6") (pin "2") (pinfunction "2_2") (pintype "passive"))
      (node (ref "C7") (pin "2") (pinfunction "2_2") (pintype "passive"))
      (node (ref "C8") (pin "2") (pinfunction "2_2") (pintype "passive"))
      (node (ref "C9") (pin "2") (pinfunction "2_2") (pintype "passive"))
      (node (ref "HANDS") (pin "2") (pinfunction "S_2") (pintype "passive"))
      (node (ref "L1") (pin "1") (pinfunction "1_1") (pintype "passive"))
      (node (ref "R12") (pin "2") (pinfunction "2_2") (pintype "passive"))
      (node (ref "R14") (pin "2") (pinfunction "2_2") (pintype "passive"))
      (node (ref "R15") (pin "2") (pinfunction "2_2") (pintype "passive"))
      (node (ref "R17") (pin "1") (pinfunction "1_1") (pintype "passive"))
      (node (ref "R4") (pin "2") (pinfunction "2_2") (pintype "passive"))
      (node (ref "R7") (pin "2") (pinfunction "2_2") (pintype "passive"))
      (node (ref "TM1") (pin "E") (pinfunction "E_E") (pintype "passive"))
      (node (ref "U$1") (pin "19") (pinfunction "VCC_19") (pintype "power_in"))
      (node (ref "U$1") (pin "20") (pinfunction "VREG_20") (pintype "passive"))
      (node (ref "U$12") (pin "5") (pinfunction "5_5") (pintype "bidirectional"))
      (node (ref "U$12") (pin "6") (pinfunction "6_6") (pintype "bidirectional"))
      (node (ref "U$13") (pin "3") (pinfunction "VCC_3") (pintype "power_in"))
      (node (ref "U$14") (pin "3") (pinfunction "VCC_3") (pintype "power_in"))
      (node (ref "U$15") (pin "3") (pinfunction "VCC_3") (pintype "power_in"))
      (node (ref "U$16") (pin "3") (pinfunction "VCC_3") (pintype "power_in"))
      (node (ref "U$2") (pin "19") (pinfunction "VCC_19") (pintype "power_in"))
      (node (ref "U$2") (pin "20") (pinfunction "VREG_20") (pintype "passive"))
      (node (ref "U1") (pin "1") (pinfunction "VDDIO_1") (pintype "power_in"))
      (node (ref "U1") (pin "14") (pinfunction "VDD_14") (pintype "power_in"))
    )
    (net (code "69") (name "unconnected-(IC1-PA4-Pad44)") (class "Default")
      (node (ref "IC1") (pin "44") (pinfunction "PA4_44") (pintype "bidirectional"))
    )
    (net (code "70") (name "unconnected-(IC1-PA5-Pad1)") (class "Default")
      (node (ref "IC1") (pin "1") (pinfunction "PA5_1") (pintype "bidirectional"))
    )
    (net (code "71") (name "unconnected-(IC1-PA6-Pad2)") (class "Default")
      (node (ref "IC1") (pin "2") (pinfunction "PA6_2") (pintype "bidirectional"))
    )
    (net (code "72") (name "unconnected-(IC1-PA7-Pad3)") (class "Default")
      (node (ref "IC1") (pin "3") (pinfunction "PA7_3") (pintype "bidirectional"))
    )
    (net (code "73") (name "unconnected-(IC1-PB0-Pad4)") (class "Default")
      (node (ref "IC1") (pin "4") (pinfunction "PB0_4") (pintype "bidirectional"))
    )
    (net (code "74") (name "unconnected-(IC1-PB1-Pad5)") (class "Default")
      (node (ref "IC1") (pin "5") (pinfunction "PB1_5") (pintype "bidirectional"))
    )
    (net (code "75") (name "unconnected-(IC1-PC2-Pad12)") (class "Default")
      (node (ref "IC1") (pin "12") (pinfunction "PC2_12") (pintype "bidirectional"))
    )
    (net (code "76") (name "unconnected-(IC1-PC3-Pad13)") (class "Default")
      (node (ref "IC1") (pin "13") (pinfunction "PC3_13") (pintype "bidirectional"))
    )
    (net (code "77") (name "unconnected-(IC1-PC4-Pad14)") (class "Default")
      (node (ref "IC1") (pin "14") (pinfunction "PC4_14") (pintype "bidirectional"))
    )
    (net (code "78") (name "unconnected-(IC1-PC5-Pad15)") (class "Default")
      (node (ref "IC1") (pin "15") (pinfunction "PC5_15") (pintype "bidirectional"))
    )
    (net (code "79") (name "unconnected-(IC1-PC6-Pad16)") (class "Default")
      (node (ref "IC1") (pin "16") (pinfunction "PC6_16") (pintype "bidirectional"))
    )
    (net (code "80") (name "unconnected-(IC1-PC7-Pad17)") (class "Default")
      (node (ref "IC1") (pin "17") (pinfunction "PC7_17") (pintype "bidirectional"))
    )
    (net (code "81") (name "unconnected-(IC1-PD1-Pad21)") (class "Default")
      (node (ref "IC1") (pin "21") (pinfunction "PD1_21") (pintype "bidirectional"))
    )
    (net (code "82") (name "unconnected-(IC1-PD4-Pad24)") (class "Default")
      (node (ref "IC1") (pin "24") (pinfunction "PD4_24") (pintype "bidirectional"))
    )
    (net (code "83") (name "unconnected-(IC1-PD6-Pad26)") (class "Default")
      (node (ref "IC1") (pin "26") (pinfunction "PD6_26") (pintype "bidirectional"))
    )
    (net (code "84") (name "unconnected-(TM1-PadA)") (class "Default")
      (node (ref "TM1") (pin "A") (pinfunction "A_A") (pintype "passive"))
    )
    (net (code "85") (name "unconnected-(U$2-SCKO-Pad11)") (class "Default")
      (node (ref "U$2") (pin "11") (pinfunction "SCKO_11") (pintype "bidirectional"))
    )
    (net (code "86") (name "unconnected-(U$2-SDTO-Pad12)") (class "Default")
      (node (ref "U$2") (pin "12") (pinfunction "SDTO_12") (pintype "bidirectional"))
    )
    (net (code "87") (name "unconnected-(U1-NC-Pad16)") (class "Default")
      (node (ref "U1") (pin "16") (pinfunction "NC_16") (pintype "no_connect"))
    )
    (net (code "88") (name "unconnected-(U1-NC_2-Pad3)") (class "Default")
      (node (ref "U1") (pin "3") (pinfunction "NC_2_3") (pintype "no_connect"))
    )
    (net (code "89") (name "unconnected-(U1-NC_3-Pad13)") (class "Default")
      (node (ref "U1") (pin "13") (pinfunction "NC_3_13") (pintype "no_connect"))
    )
    (net (code "90") (name "unconnected-(U1-NC_4-Pad15)") (class "Default")
      (node (ref "U1") (pin "15") (pinfunction "NC_4_15") (pintype "no_connect"))
    )
    (net (code "91") (name "unconnected-(U1-NC_5-Pad8)") (class "Default")
      (node (ref "U1") (pin "8") (pinfunction "NC_5_8") (pintype "no_connect"))
    )
  )
)
